# source_eagle.net
KiCad netlist of a schematic drawn in EAGLE
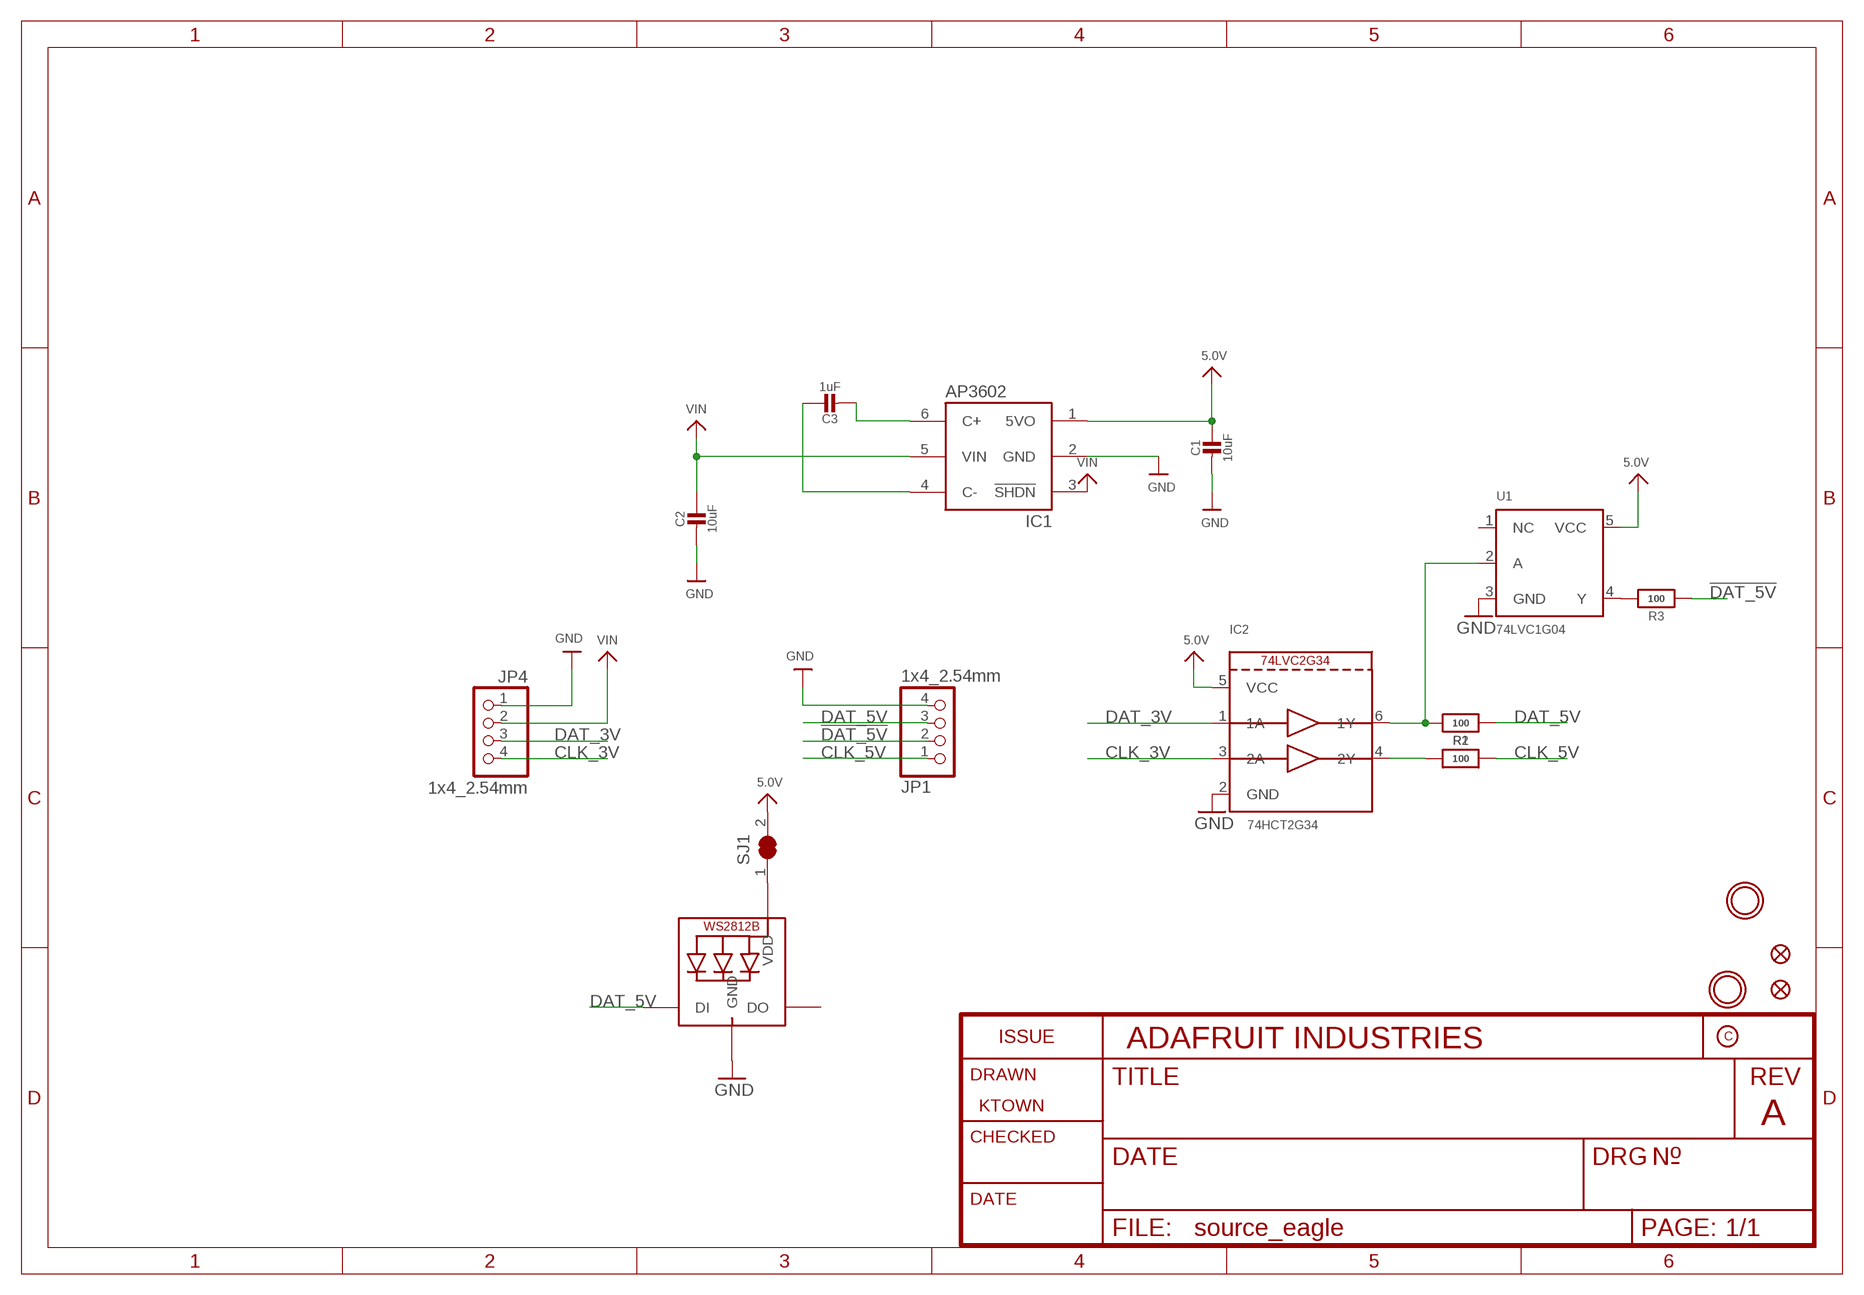
[diagram p0: schematic, sheet 1]

(export (version "E")
  (design (tool "Eeschema 10.0.6"))
  (components
    (comp (ref "C1")
      (value "10uF")
      (footprint "eagle-import:0805-NO")
      (libsource (lib "eagle-import") (part "CAP_CERAMIC0805-NOOUTLINE"))
    )
    (comp (ref "C2")
      (value "10uF")
      (footprint "eagle-import:0805-NO")
      (libsource (lib "eagle-import") (part "CAP_CERAMIC0805-NOOUTLINE"))
    )
    (comp (ref "C3")
      (value "1uF")
      (footprint "eagle-import:0603-NO_WIDE")
      (libsource (lib "eagle-import") (part "CAP_CERAMIC_0603WIDE"))
    )
    (comp (ref "FID1")
      (value "FIDUCIAL_0.5MM")
      (footprint "eagle-import:FIDUCIAL_0.5MM")
      (libsource (lib "eagle-import") (part "FIDUCIAL_0.5MM"))
    )
    (comp (ref "FID2")
      (value "FIDUCIAL_0.5MM")
      (footprint "eagle-import:FIDUCIAL_0.5MM")
      (libsource (lib "eagle-import") (part "FIDUCIAL_0.5MM"))
    )
    (comp (ref "IC1")
      (value "AP3602")
      (footprint "eagle-import:SOT23-6")
      (libsource (lib "eagle-import") (part "AP3602"))
    )
    (comp (ref "IC2")
      (value "74HCT2G34")
      (footprint "eagle-import:SC70-6L")
      (libsource (lib "eagle-import") (part "74LVC2G34"))
    )
    (comp (ref "JP1")
      (value "1x4_2.54mm")
      (footprint "eagle-import:1X04_2.54MMTERMINAL")
      (libsource (lib "eagle-import") (part "HEADER-1X4_254MMTERM"))
    )
    (comp (ref "JP4")
      (value "1x4_2.54mm")
      (footprint "eagle-import:1X04_2.54MMTERMINAL")
      (libsource (lib "eagle-import") (part "HEADER-1X4_254MMTERM"))
    )
    (comp (ref "LED1")
      (value "WS2812B_SK6805_1515")
      (footprint "eagle-import:SK6805_1515")
      (libsource (lib "eagle-import") (part "WS2812B_SK6805_1515"))
    )
    (comp (ref "R1")
      (value "100")
      (footprint "eagle-import:_0402NO")
      (libsource (lib "eagle-import") (part "RESISTOR_0402NO"))
    )
    (comp (ref "R2")
      (value "100")
      (footprint "eagle-import:_0402NO")
      (libsource (lib "eagle-import") (part "RESISTOR_0402NO"))
    )
    (comp (ref "R3")
      (value "100")
      (footprint "eagle-import:_0402NO")
      (libsource (lib "eagle-import") (part "RESISTOR_0402NO"))
    )
    (comp (ref "SJ1")
      (value "SOLDERJUMPER_CLOSED")
      (footprint "eagle-import:SOLDERJUMPER_CLOSEDWIRE")
      (libsource (lib "eagle-import") (part "SOLDERJUMPER_CLOSED"))
    )
    (comp (ref "U$6")
      (value "MOUNTINGHOLE2.5")
      (footprint "eagle-import:MOUNTINGHOLE_2.5_PLATED")
      (libsource (lib "eagle-import") (part "MOUNTINGHOLE2.5"))
    )
    (comp (ref "U$9")
      (value "MOUNTINGHOLE2.5")
      (footprint "eagle-import:MOUNTINGHOLE_2.5_PLATED")
      (libsource (lib "eagle-import") (part "MOUNTINGHOLE2.5"))
    )
    (comp (ref "U1")
      (value "74LVC1G04")
      (footprint "eagle-import:SC70-5")
      (libsource (lib "eagle-import") (part "74LVC1G04SC-70"))
    )
  )
  (nets
    (net (code "1") (name "/CLK_3V") (class "Default")
      (node (ref "IC2") (pin "3") (pinfunction "2A_3") (pintype "input"))
      (node (ref "JP4") (pin "4") (pinfunction "4_4") (pintype "passive"))
    )
    (net (code "2") (name "/CLK_5V") (class "Default")
      (node (ref "JP1") (pin "1") (pinfunction "1_1") (pintype "passive"))
      (node (ref "R1") (pin "2") (pinfunction "2_2") (pintype "passive"))
    )
    (net (code "3") (name "/DAT_3V") (class "Default")
      (node (ref "IC2") (pin "1") (pinfunction "1A_1") (pintype "input"))
      (node (ref "JP4") (pin "3") (pinfunction "3_3") (pintype "passive"))
    )
    (net (code "4") (name "/DAT_5V") (class "Default")
      (node (ref "JP1") (pin "3") (pinfunction "3_3") (pintype "passive"))
      (node (ref "LED1") (pin "1") (pinfunction "DI_1") (pintype "input"))
      (node (ref "R2") (pin "2") (pinfunction "2_2") (pintype "passive"))
    )
    (net (code "5") (name "/~{DAT_5V}") (class "Default")
      (node (ref "JP1") (pin "2") (pinfunction "2_2") (pintype "passive"))
      (node (ref "R3") (pin "2") (pinfunction "2_2") (pintype "passive"))
    )
    (net (code "6") (name "5.0V") (class "Default")
      (node (ref "C1") (pin "1") (pinfunction "1_1") (pintype "passive"))
      (node (ref "IC1") (pin "1") (pinfunction "5VO_1") (pintype "power_in"))
      (node (ref "IC2") (pin "5") (pinfunction "VCC_5") (pintype "power_in"))
      (node (ref "SJ1") (pin "2") (pinfunction "2_2") (pintype "passive"))
      (node (ref "U1") (pin "5") (pinfunction "VCC_5") (pintype "power_in"))
    )
    (net (code "7") (name "GND") (class "Default")
      (node (ref "C1") (pin "2") (pinfunction "2_2") (pintype "passive"))
      (node (ref "C2") (pin "2") (pinfunction "2_2") (pintype "passive"))
      (node (ref "IC1") (pin "2") (pinfunction "GND_2") (pintype "power_in"))
      (node (ref "IC2") (pin "2") (pinfunction "GND_2") (pintype "power_in"))
      (node (ref "JP1") (pin "4") (pinfunction "4_4") (pintype "passive"))
      (node (ref "JP4") (pin "1") (pinfunction "1_1") (pintype "passive"))
      (node (ref "LED1") (pin "4") (pinfunction "GND_4") (pintype "power_in"))
      (node (ref "U1") (pin "3") (pinfunction "GND_3") (pintype "power_in"))
    )
    (net (code "8") (name "Net-(IC1-C+)") (class "Default")
      (node (ref "C3") (pin "2") (pinfunction "2_2") (pintype "passive"))
      (node (ref "IC1") (pin "6") (pinfunction "C+_6") (pintype "bidirectional"))
    )
    (net (code "9") (name "Net-(IC1-C-)") (class "Default")
      (node (ref "C3") (pin "1") (pinfunction "1_1") (pintype "passive"))
      (node (ref "IC1") (pin "4") (pinfunction "C-_4") (pintype "bidirectional"))
    )
    (net (code "10") (name "Net-(IC2-1Y)") (class "Default")
      (node (ref "IC2") (pin "6") (pinfunction "1Y_6") (pintype "output"))
      (node (ref "R2") (pin "1") (pinfunction "1_1") (pintype "passive"))
      (node (ref "U1") (pin "2") (pinfunction "A_2") (pintype "bidirectional"))
    )
    (net (code "11") (name "Net-(IC2-2Y)") (class "Default")
      (node (ref "IC2") (pin "4") (pinfunction "2Y_4") (pintype "output"))
      (node (ref "R1") (pin "1") (pinfunction "1_1") (pintype "passive"))
    )
    (net (code "12") (name "Net-(LED1-VDD)") (class "Default")
      (node (ref "LED1") (pin "2") (pinfunction "VDD_2") (pintype "power_in"))
      (node (ref "SJ1") (pin "1") (pinfunction "1_1") (pintype "passive"))
    )
    (net (code "13") (name "Net-(U1-Y)") (class "Default")
      (node (ref "R3") (pin "1") (pinfunction "1_1") (pintype "passive"))
      (node (ref "U1") (pin "4") (pinfunction "Y_4") (pintype "bidirectional"))
    )
    (net (code "14") (name "VIN") (class "Default")
      (node (ref "C2") (pin "1") (pinfunction "1_1") (pintype "passive"))
      (node (ref "IC1") (pin "3") (pinfunction "~{SHDN}_3") (pintype "input"))
      (node (ref "IC1") (pin "5") (pinfunction "VIN_5") (pintype "power_in"))
      (node (ref "JP4") (pin "2") (pinfunction "2_2") (pintype "passive"))
    )
    (net (code "15") (name "unconnected-(LED1-DO-Pad3)") (class "Default")
      (node (ref "LED1") (pin "3") (pinfunction "DO_3") (pintype "output"))
    )
    (net (code "16") (name "unconnected-(U1-NC-Pad1)") (class "Default")
      (node (ref "U1") (pin "1") (pinfunction "NC_1") (pintype "no_connect"))
    )
  )
)
